# power_injector_rev_b.net
KiCad netlist of a schematic drawn in EAGLE
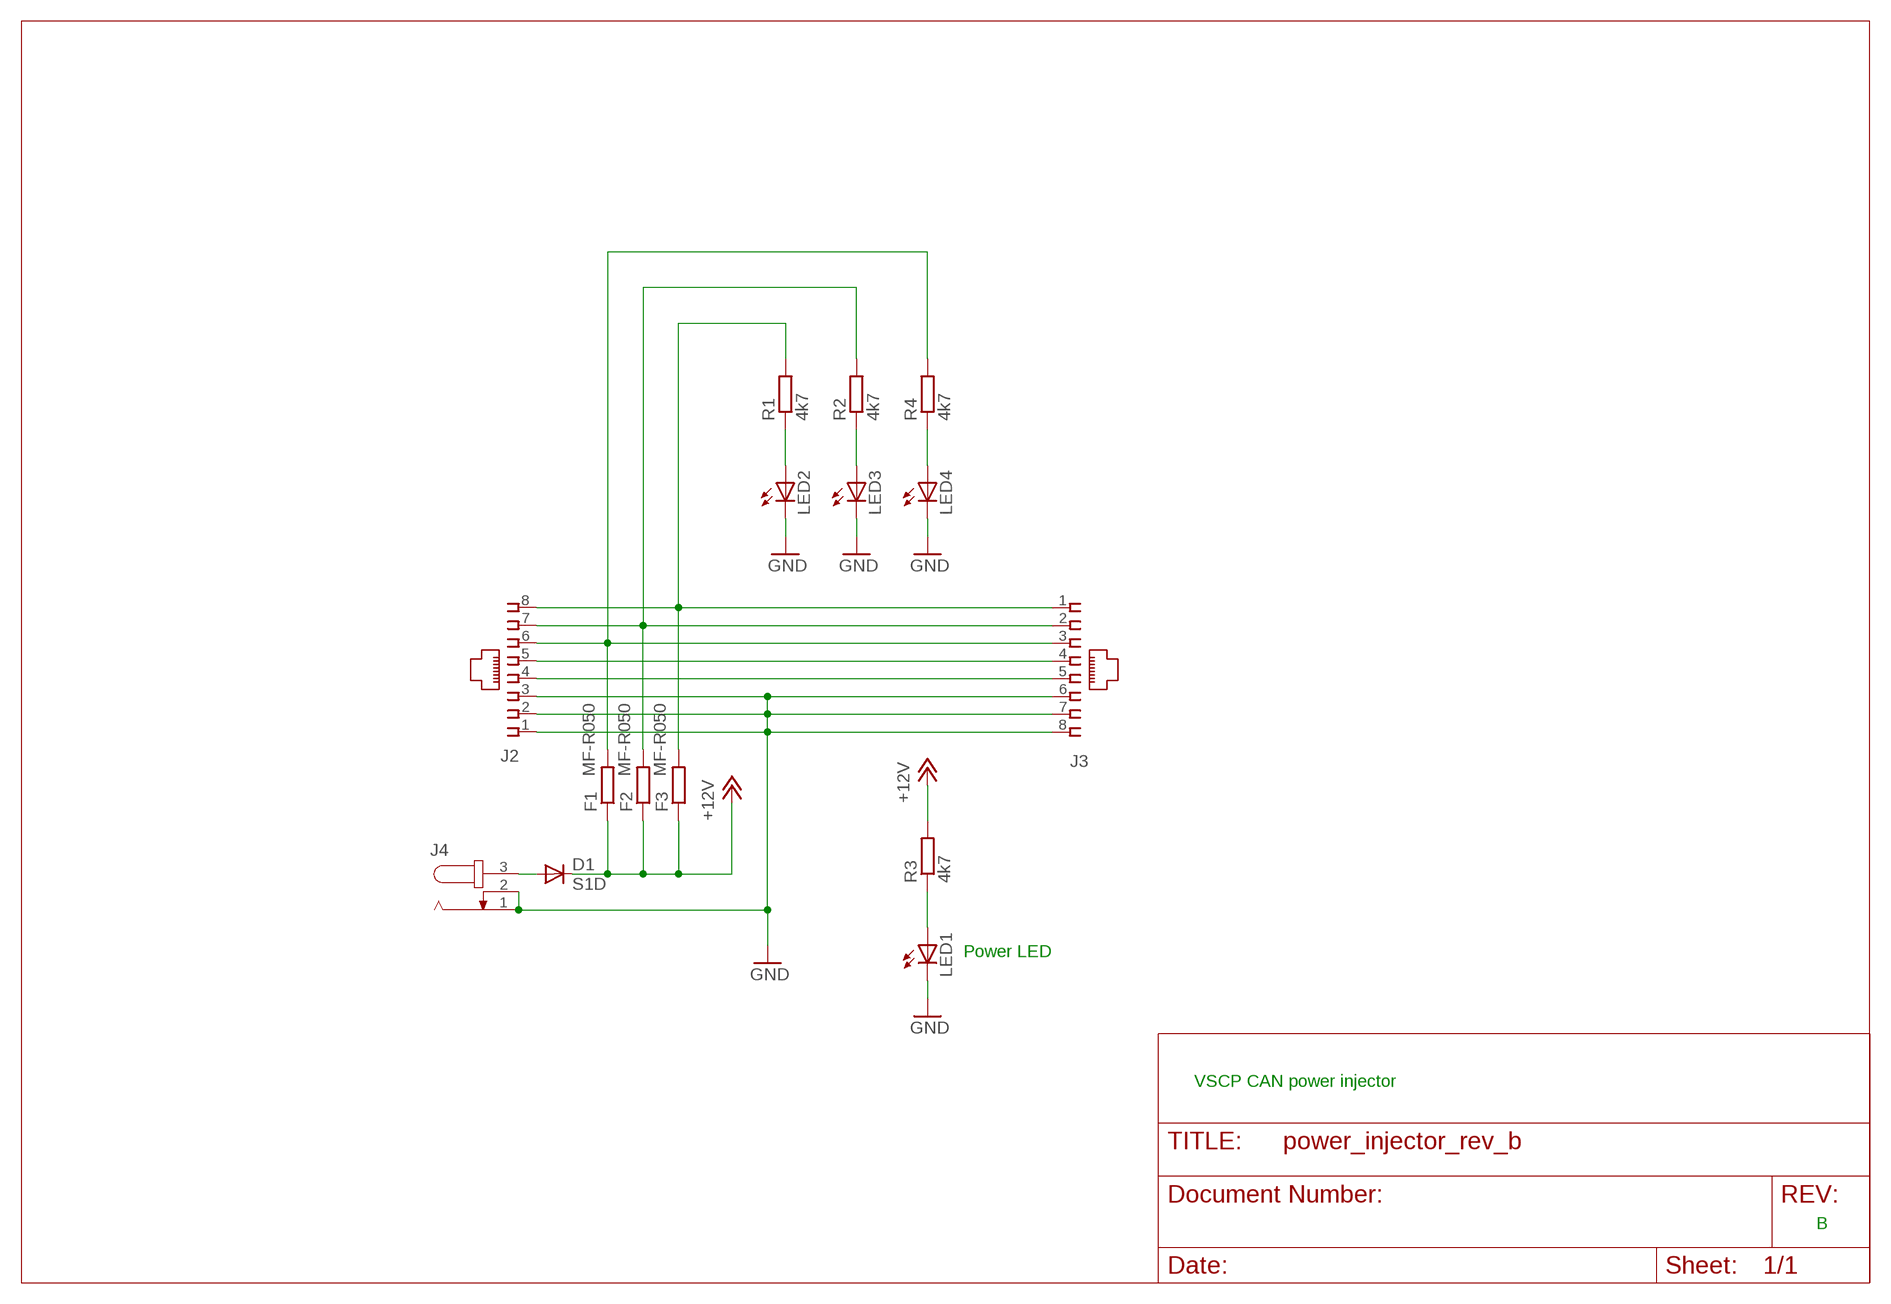
[diagram p0: schematic, sheet 1]

(export (version "E")
  (design (tool "Eeschema 10.0.6"))
  (components
    (comp (ref "D1")
      (value "S1D")
      (footprint "eagle-import:SMB")
      (libsource (lib "eagle-import") (part "DIODE-SMB"))
    )
    (comp (ref "F1")
      (value "MF-R050")
      (footprint "eagle-import:0204_5")
      (libsource (lib "eagle-import") (part "R-EU_0204/5"))
    )
    (comp (ref "F2")
      (value "MF-R050")
      (footprint "eagle-import:0204_5")
      (libsource (lib "eagle-import") (part "R-EU_0204/5"))
    )
    (comp (ref "F3")
      (value "MF-R050")
      (footprint "eagle-import:0204_5")
      (libsource (lib "eagle-import") (part "R-EU_0204/5"))
    )
    (comp (ref "J2")
      (value "A00-108-220-450")
      (footprint "eagle-import:RJ-45")
      (libsource (lib "eagle-import") (part "A00-108-220-450"))
    )
    (comp (ref "J3")
      (value "A00-108-220-450")
      (footprint "eagle-import:RJ-45")
      (libsource (lib "eagle-import") (part "A00-108-220-450"))
    )
    (comp (ref "J4")
      (value "JACK-PLUG0")
      (footprint "eagle-import:SPC4077")
      (libsource (lib "eagle-import") (part "JACK-PLUG0"))
    )
    (comp (ref "LED1")
      (value "LEDCHIP-LED0805")
      (footprint "eagle-import:CHIP-LED0805")
      (libsource (lib "eagle-import") (part "LEDCHIP-LED0805"))
    )
    (comp (ref "LED2")
      (value "LEDCHIP-LED0805")
      (footprint "eagle-import:CHIP-LED0805")
      (libsource (lib "eagle-import") (part "LEDCHIP-LED0805"))
    )
    (comp (ref "LED3")
      (value "LEDCHIP-LED0805")
      (footprint "eagle-import:CHIP-LED0805")
      (libsource (lib "eagle-import") (part "LEDCHIP-LED0805"))
    )
    (comp (ref "LED4")
      (value "LEDCHIP-LED0805")
      (footprint "eagle-import:CHIP-LED0805")
      (libsource (lib "eagle-import") (part "LEDCHIP-LED0805"))
    )
    (comp (ref "R1")
      (value "4k7")
      (footprint "eagle-import:R0805")
      (libsource (lib "eagle-import") (part "R-EU_R0805"))
    )
    (comp (ref "R2")
      (value "4k7")
      (footprint "eagle-import:R0805")
      (libsource (lib "eagle-import") (part "R-EU_R0805"))
    )
    (comp (ref "R3")
      (value "4k7")
      (footprint "eagle-import:R0805")
      (libsource (lib "eagle-import") (part "R-EU_R0805"))
    )
    (comp (ref "R4")
      (value "4k7")
      (footprint "eagle-import:R0805")
      (libsource (lib "eagle-import") (part "R-EU_R0805"))
    )
  )
  (nets
    (net (code "1") (name "+12V") (class "Default")
      (node (ref "D1") (pin "C") (pinfunction "C_C") (pintype "passive"))
      (node (ref "F1") (pin "1") (pinfunction "1_1") (pintype "passive"))
      (node (ref "F2") (pin "1") (pinfunction "1_1") (pintype "passive"))
      (node (ref "F3") (pin "1") (pinfunction "1_1") (pintype "passive"))
      (node (ref "R3") (pin "2") (pinfunction "2_2") (pintype "passive"))
    )
    (net (code "2") (name "GND") (class "Default")
      (node (ref "J2") (pin "1") (pinfunction "1_1") (pintype "passive"))
      (node (ref "J2") (pin "2") (pinfunction "2_2") (pintype "passive"))
      (node (ref "J2") (pin "3") (pinfunction "3_3") (pintype "passive"))
      (node (ref "J3") (pin "6") (pinfunction "6_6") (pintype "passive"))
      (node (ref "J3") (pin "7") (pinfunction "7_7") (pintype "passive"))
      (node (ref "J3") (pin "8") (pinfunction "8_8") (pintype "passive"))
      (node (ref "J4") (pin "1") (pinfunction "1_1") (pintype "passive"))
      (node (ref "J4") (pin "2") (pinfunction "2_2") (pintype "passive"))
      (node (ref "LED1") (pin "C") (pinfunction "C_C") (pintype "passive"))
      (node (ref "LED2") (pin "C") (pinfunction "C_C") (pintype "passive"))
      (node (ref "LED3") (pin "C") (pinfunction "C_C") (pintype "passive"))
      (node (ref "LED4") (pin "C") (pinfunction "C_C") (pintype "passive"))
    )
    (net (code "3") (name "Net-(D1-PadA)") (class "Default")
      (node (ref "D1") (pin "A") (pinfunction "A_A") (pintype "passive"))
      (node (ref "J4") (pin "3") (pinfunction "3_3") (pintype "passive"))
    )
    (net (code "4") (name "Net-(F1-Pad2)") (class "Default")
      (node (ref "F1") (pin "2") (pinfunction "2_2") (pintype "passive"))
      (node (ref "J2") (pin "6") (pinfunction "6_6") (pintype "passive"))
      (node (ref "J3") (pin "3") (pinfunction "3_3") (pintype "passive"))
      (node (ref "R4") (pin "2") (pinfunction "2_2") (pintype "passive"))
    )
    (net (code "5") (name "Net-(F2-Pad2)") (class "Default")
      (node (ref "F2") (pin "2") (pinfunction "2_2") (pintype "passive"))
      (node (ref "J2") (pin "7") (pinfunction "7_7") (pintype "passive"))
      (node (ref "J3") (pin "2") (pinfunction "2_2") (pintype "passive"))
      (node (ref "R2") (pin "2") (pinfunction "2_2") (pintype "passive"))
    )
    (net (code "6") (name "Net-(F3-Pad2)") (class "Default")
      (node (ref "F3") (pin "2") (pinfunction "2_2") (pintype "passive"))
      (node (ref "J2") (pin "8") (pinfunction "8_8") (pintype "passive"))
      (node (ref "J3") (pin "1") (pinfunction "1_1") (pintype "passive"))
      (node (ref "R1") (pin "2") (pinfunction "2_2") (pintype "passive"))
    )
    (net (code "7") (name "Net-(J2-Pad4)") (class "Default")
      (node (ref "J2") (pin "4") (pinfunction "4_4") (pintype "passive"))
      (node (ref "J3") (pin "5") (pinfunction "5_5") (pintype "passive"))
    )
    (net (code "8") (name "Net-(J2-Pad5)") (class "Default")
      (node (ref "J2") (pin "5") (pinfunction "5_5") (pintype "passive"))
      (node (ref "J3") (pin "4") (pinfunction "4_4") (pintype "passive"))
    )
    (net (code "9") (name "Net-(LED1-PadA)") (class "Default")
      (node (ref "LED1") (pin "A") (pinfunction "A_A") (pintype "passive"))
      (node (ref "R3") (pin "1") (pinfunction "1_1") (pintype "passive"))
    )
    (net (code "10") (name "Net-(LED2-PadA)") (class "Default")
      (node (ref "LED2") (pin "A") (pinfunction "A_A") (pintype "passive"))
      (node (ref "R1") (pin "1") (pinfunction "1_1") (pintype "passive"))
    )
    (net (code "11") (name "Net-(LED3-PadA)") (class "Default")
      (node (ref "LED3") (pin "A") (pinfunction "A_A") (pintype "passive"))
      (node (ref "R2") (pin "1") (pinfunction "1_1") (pintype "passive"))
    )
    (net (code "12") (name "Net-(LED4-PadA)") (class "Default")
      (node (ref "LED4") (pin "A") (pinfunction "A_A") (pintype "passive"))
      (node (ref "R4") (pin "1") (pinfunction "1_1") (pintype "passive"))
    )
  )
)
